# AVR_GPS_APRS_Tracker.net
KiCad netlist of a schematic drawn in EAGLE
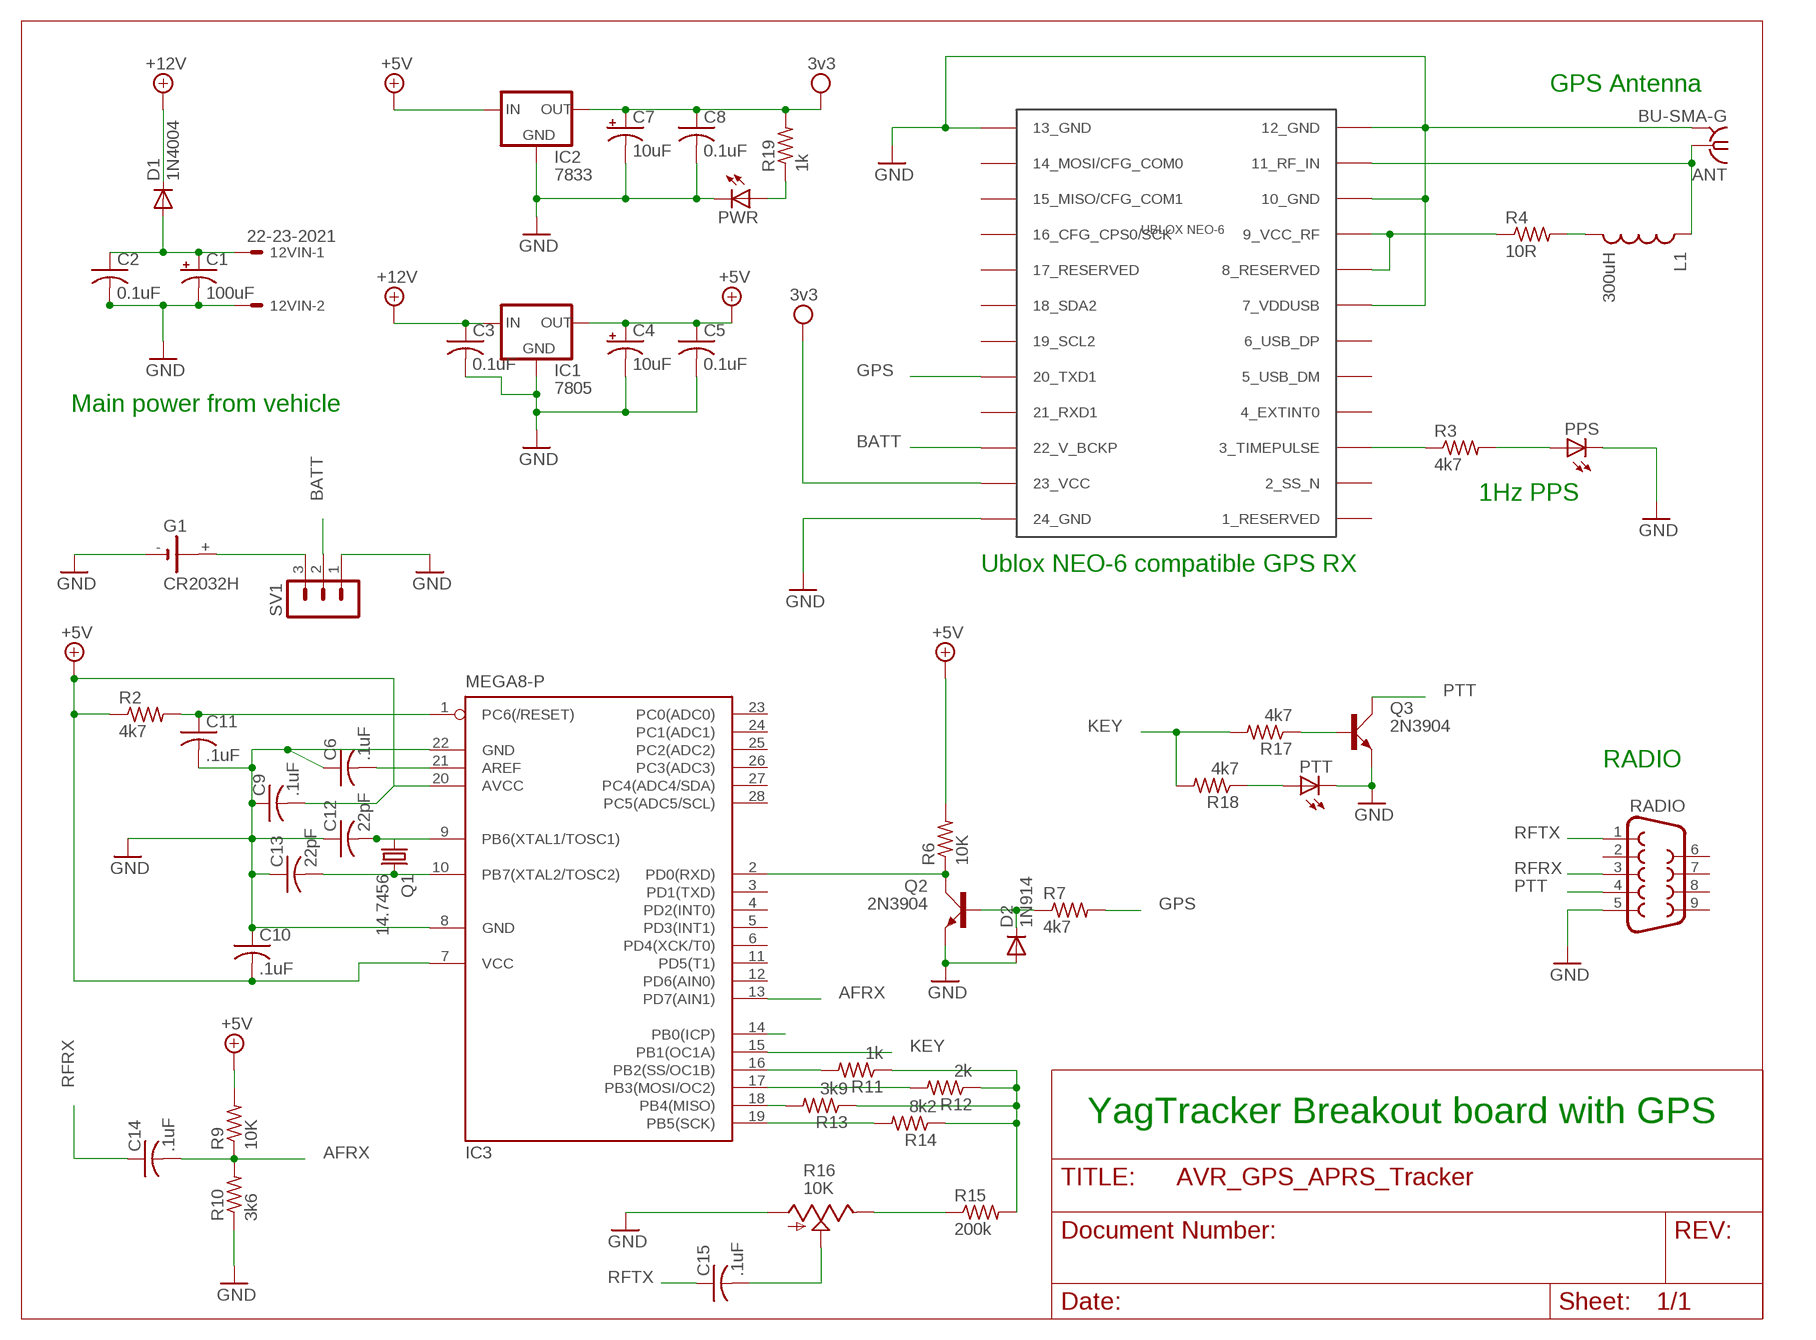
[diagram p0: schematic, sheet 1]

(export (version "E")
  (design (tool "Eeschema 10.0.6"))
  (components
    (comp (ref "12VIN")
      (value "22-23-2021")
      (footprint "eagle-import:22-23-2021")
      (fields (field (name "MF") "MOLEX"))
      (libsource (lib "eagle-import") (part "22-23-2021"))
    )
    (comp (ref "ANT")
      (value "BU-SMA-G")
      (footprint "eagle-import:BU-SMA-G")
      (libsource (lib "eagle-import") (part "BU-SMA-G"))
    )
    (comp (ref "C1")
      (value "100uF")
      (footprint "eagle-import:CPOL-RADIAL-10UF-25V")
      (libsource (lib "eagle-import") (part "CAP_POLPTH2"))
    )
    (comp (ref "C2")
      (value "0.1uF")
      (footprint "eagle-import:C025-025X050")
      (libsource (lib "eagle-import") (part "C-US025-025X050"))
    )
    (comp (ref "C3")
      (value "0.1uF")
      (footprint "eagle-import:C025-025X050")
      (libsource (lib "eagle-import") (part "C-US025-025X050"))
    )
    (comp (ref "C4")
      (value "10uF")
      (footprint "eagle-import:CPOL-RADIAL-10UF-25V")
      (libsource (lib "eagle-import") (part "CAP_POLPTH2"))
    )
    (comp (ref "C5")
      (value "0.1uF")
      (footprint "eagle-import:C025-025X050")
      (libsource (lib "eagle-import") (part "C-US025-025X050"))
    )
    (comp (ref "C6")
      (value ".1uF")
      (footprint "eagle-import:C025-025X050")
      (libsource (lib "eagle-import") (part "C-US025-025X050"))
    )
    (comp (ref "C7")
      (value "10uF")
      (footprint "eagle-import:CPOL-RADIAL-10UF-25V")
      (libsource (lib "eagle-import") (part "CAP_POLPTH2"))
    )
    (comp (ref "C8")
      (value "0.1uF")
      (footprint "eagle-import:C025-025X050")
      (libsource (lib "eagle-import") (part "C-US025-025X050"))
    )
    (comp (ref "C9")
      (value ".1uF")
      (footprint "eagle-import:C025-025X050")
      (libsource (lib "eagle-import") (part "C-US025-025X050"))
    )
    (comp (ref "C10")
      (value ".1uF")
      (footprint "eagle-import:C025-025X050")
      (libsource (lib "eagle-import") (part "C-US025-025X050"))
    )
    (comp (ref "C11")
      (value ".1uF")
      (footprint "eagle-import:C025-025X050")
      (libsource (lib "eagle-import") (part "C-US025-025X050"))
    )
    (comp (ref "C12")
      (value "22pF")
      (footprint "eagle-import:C025-025X050")
      (libsource (lib "eagle-import") (part "C-US025-025X050"))
    )
    (comp (ref "C13")
      (value "22pF")
      (footprint "eagle-import:C025-025X050")
      (libsource (lib "eagle-import") (part "C-US025-025X050"))
    )
    (comp (ref "C14")
      (value ".1uF")
      (footprint "eagle-import:C025-025X050")
      (libsource (lib "eagle-import") (part "C-US025-025X050"))
    )
    (comp (ref "C15")
      (value ".1uF")
      (footprint "eagle-import:C025-025X050")
      (libsource (lib "eagle-import") (part "C-US025-025X050"))
    )
    (comp (ref "D1")
      (value "1N4004")
      (footprint "eagle-import:DO41-10")
      (libsource (lib "eagle-import") (part "1N4004"))
    )
    (comp (ref "D2")
      (value "1N914")
      (footprint "eagle-import:D-2.5")
      (libsource (lib "eagle-import") (part "DIODE-D-2.5"))
    )
    (comp (ref "G1")
      (value "CR2032H")
      (footprint "eagle-import:CR2032H")
      (libsource (lib "eagle-import") (part "CR2032H"))
    )
    (comp (ref "IC1")
      (value "7805")
      (footprint "eagle-import:TO-220-ALT")
      (libsource (lib "eagle-import") (part "V_REG_78XX-TO-220"))
    )
    (comp (ref "IC2")
      (value "7833")
      (footprint "eagle-import:TO-220-ALT")
      (libsource (lib "eagle-import") (part "V_REG_78XX-TO-220"))
    )
    (comp (ref "IC3")
      (value "MEGA8-P")
      (footprint "eagle-import:DIL28-3")
      (libsource (lib "eagle-import") (part "MEGA8-P"))
    )
    (comp (ref "L1")
      (value "300uH")
      (footprint "eagle-import:0805")
      (libsource (lib "eagle-import") (part "INDUCTOR0805"))
    )
    (comp (ref "PPS")
      (value "LED0603")
      (footprint "eagle-import:LED-0603")
      (libsource (lib "eagle-import") (part "LED0603"))
    )
    (comp (ref "PTT")
      (value "LED3MM")
      (footprint "eagle-import:LED3MM")
      (libsource (lib "eagle-import") (part "LED3MM"))
    )
    (comp (ref "PWR")
      (value "LED3MM")
      (footprint "eagle-import:LED3MM")
      (libsource (lib "eagle-import") (part "LED3MM"))
    )
    (comp (ref "Q1")
      (value "14.7456")
      (footprint "eagle-import:HC49_S")
      (libsource (lib "eagle-import") (part "CRYSTALHC49S"))
    )
    (comp (ref "Q2")
      (value "2N3904")
      (footprint "eagle-import:TO92D")
      (libsource (lib "eagle-import") (part "2N3904"))
    )
    (comp (ref "Q3")
      (value "2N3904")
      (footprint "eagle-import:TO92D")
      (libsource (lib "eagle-import") (part "2N3904"))
    )
    (comp (ref "R2")
      (value "4k7")
      (footprint "eagle-import:0207_2V")
      (libsource (lib "eagle-import") (part "R-US_0207/2V"))
    )
    (comp (ref "R3")
      (value "4k7")
      (footprint "eagle-import:M0805")
      (libsource (lib "eagle-import") (part "R-US_M0805"))
    )
    (comp (ref "R4")
      (value "10R")
      (footprint "eagle-import:M0805")
      (libsource (lib "eagle-import") (part "R-US_M0805"))
    )
    (comp (ref "R6")
      (value "10K")
      (footprint "eagle-import:0207_2V")
      (libsource (lib "eagle-import") (part "R-US_0207/2V"))
    )
    (comp (ref "R7")
      (value "4k7")
      (footprint "eagle-import:0207_2V")
      (libsource (lib "eagle-import") (part "R-US_0207/2V"))
    )
    (comp (ref "R9")
      (value "10K")
      (footprint "eagle-import:0207_2V")
      (libsource (lib "eagle-import") (part "R-US_0207/2V"))
    )
    (comp (ref "R10")
      (value "3k6")
      (footprint "eagle-import:0207_2V")
      (libsource (lib "eagle-import") (part "R-US_0207/2V"))
    )
    (comp (ref "R11")
      (value "1k")
      (footprint "eagle-import:0207_2V")
      (libsource (lib "eagle-import") (part "R-US_0207/2V"))
    )
    (comp (ref "R12")
      (value "2k")
      (footprint "eagle-import:0207_2V")
      (libsource (lib "eagle-import") (part "R-US_0207/2V"))
    )
    (comp (ref "R13")
      (value "3k9")
      (footprint "eagle-import:0207_2V")
      (libsource (lib "eagle-import") (part "R-US_0207/2V"))
    )
    (comp (ref "R14")
      (value "8k2")
      (footprint "eagle-import:0207_2V")
      (libsource (lib "eagle-import") (part "R-US_0207/2V"))
    )
    (comp (ref "R15")
      (value "200k")
      (footprint "eagle-import:0207_2V")
      (libsource (lib "eagle-import") (part "R-US_0207/2V"))
    )
    (comp (ref "R16")
      (value "10K")
      (footprint "eagle-import:CA6V")
      (libsource (lib "eagle-import") (part "TRIM_US-CA6V"))
    )
    (comp (ref "R17")
      (value "4k7")
      (footprint "eagle-import:0207_2V")
      (libsource (lib "eagle-import") (part "R-US_0207/2V"))
    )
    (comp (ref "R18")
      (value "4k7")
      (footprint "eagle-import:0207_2V")
      (libsource (lib "eagle-import") (part "R-US_0207/2V"))
    )
    (comp (ref "R19")
      (value "1k")
      (footprint "eagle-import:0207_2V")
      (libsource (lib "eagle-import") (part "R-US_0207/2V"))
    )
    (comp (ref "RADIO")
      (value "F09HP")
      (footprint "eagle-import:F09HP")
      (libsource (lib "eagle-import") (part "F09HP"))
    )
    (comp (ref "SV1")
      (value "MA03-1")
      (footprint "eagle-import:MA03-1")
      (libsource (lib "eagle-import") (part "MA03-1"))
    )
    (comp (ref "U$1")
      (value "UBLOX_NEO-6")
      (footprint "eagle-import:UBLOX_NEO-6P")
      (libsource (lib "eagle-import") (part "UBLOX_NEO-6"))
    )
  )
  (nets
    (net (code "1") (name "+5V") (class "Default")
      (node (ref "C10") (pin "2") (pinfunction "2_2") (pintype "passive"))
      (node (ref "C4") (pin "1") (pinfunction "+_1") (pintype "passive"))
      (node (ref "C5") (pin "1") (pinfunction "1_1") (pintype "passive"))
      (node (ref "C9") (pin "2") (pinfunction "2_2") (pintype "passive"))
      (node (ref "IC1") (pin "OUT") (pinfunction "OUT_OUT") (pintype "output"))
      (node (ref "IC2") (pin "IN") (pinfunction "IN_IN") (pintype "input"))
      (node (ref "IC3") (pin "20") (pinfunction "AVCC_20") (pintype "power_in"))
      (node (ref "IC3") (pin "7") (pinfunction "VCC_7") (pintype "power_in"))
      (node (ref "R2") (pin "1") (pinfunction "1_1") (pintype "passive"))
      (node (ref "R6") (pin "2") (pinfunction "2_2") (pintype "passive"))
      (node (ref "R9") (pin "2") (pinfunction "2_2") (pintype "passive"))
    )
    (net (code "2") (name "+12V") (class "Default")
      (node (ref "C3") (pin "1") (pinfunction "1_1") (pintype "passive"))
      (node (ref "D1") (pin "C") (pinfunction "C_C") (pintype "passive"))
      (node (ref "IC1") (pin "IN") (pinfunction "IN_IN") (pintype "input"))
    )
    (net (code "3") (name "/AFRX") (class "Default")
      (node (ref "C14") (pin "2") (pinfunction "2_2") (pintype "passive"))
      (node (ref "IC3") (pin "13") (pinfunction "PD7(AIN1)_13") (pintype "bidirectional"))
      (node (ref "R10") (pin "2") (pinfunction "2_2") (pintype "passive"))
      (node (ref "R9") (pin "1") (pinfunction "1_1") (pintype "passive"))
    )
    (net (code "4") (name "/BATT") (class "Default")
      (node (ref "SV1") (pin "2") (pinfunction "2_2") (pintype "passive"))
      (node (ref "U$1") (pin "22_V_BCKP") (pinfunction "22_V_BCKP_22_V_BCKP") (pintype "bidirectional"))
    )
    (net (code "5") (name "/GPS") (class "Default")
      (node (ref "R7") (pin "2") (pinfunction "2_2") (pintype "passive"))
      (node (ref "U$1") (pin "20_TXD1") (pinfunction "20_TXD1_20_TXD1") (pintype "bidirectional"))
    )
    (net (code "6") (name "/KEY") (class "Default")
      (node (ref "IC3") (pin "15") (pinfunction "PB1(OC1A)_15") (pintype "bidirectional"))
      (node (ref "R17") (pin "2") (pinfunction "2_2") (pintype "passive"))
      (node (ref "R18") (pin "2") (pinfunction "2_2") (pintype "passive"))
    )
    (net (code "7") (name "/PTT") (class "Default")
      (node (ref "Q3") (pin "C") (pinfunction "C_C") (pintype "passive"))
      (node (ref "RADIO") (pin "4") (pinfunction "4_4") (pintype "passive"))
    )
    (net (code "8") (name "/RFRX") (class "Default")
      (node (ref "C14") (pin "1") (pinfunction "1_1") (pintype "passive"))
      (node (ref "RADIO") (pin "3") (pinfunction "3_3") (pintype "passive"))
    )
    (net (code "9") (name "/RFTX") (class "Default")
      (node (ref "C15") (pin "1") (pinfunction "1_1") (pintype "passive"))
      (node (ref "RADIO") (pin "1") (pinfunction "1_1") (pintype "passive"))
    )
    (net (code "10") (name "3v3") (class "Default")
      (node (ref "C7") (pin "1") (pinfunction "+_1") (pintype "passive"))
      (node (ref "C8") (pin "1") (pinfunction "1_1") (pintype "passive"))
      (node (ref "IC2") (pin "OUT") (pinfunction "OUT_OUT") (pintype "output"))
      (node (ref "R19") (pin "2") (pinfunction "2_2") (pintype "passive"))
      (node (ref "U$1") (pin "23_VCC") (pinfunction "23_VCC_23_VCC") (pintype "bidirectional"))
    )
    (net (code "11") (name "GND") (class "Default")
      (node (ref "12VIN") (pin "2") (pinfunction "S_2") (pintype "passive"))
      (node (ref "ANT") (pin "2") (pinfunction "GND_2") (pintype "power_in"))
      (node (ref "C1") (pin "2") (pinfunction "-_2") (pintype "passive"))
      (node (ref "C10") (pin "1") (pinfunction "1_1") (pintype "passive"))
      (node (ref "C11") (pin "2") (pinfunction "2_2") (pintype "passive"))
      (node (ref "C12") (pin "1") (pinfunction "1_1") (pintype "passive"))
      (node (ref "C13") (pin "1") (pinfunction "1_1") (pintype "passive"))
      (node (ref "C2") (pin "2") (pinfunction "2_2") (pintype "passive"))
      (node (ref "C3") (pin "2") (pinfunction "2_2") (pintype "passive"))
      (node (ref "C4") (pin "2") (pinfunction "-_2") (pintype "passive"))
      (node (ref "C5") (pin "2") (pinfunction "2_2") (pintype "passive"))
      (node (ref "C6") (pin "1") (pinfunction "1_1") (pintype "passive"))
      (node (ref "C7") (pin "2") (pinfunction "-_2") (pintype "passive"))
      (node (ref "C8") (pin "2") (pinfunction "2_2") (pintype "passive"))
      (node (ref "C9") (pin "1") (pinfunction "1_1") (pintype "passive"))
      (node (ref "D2") (pin "A") (pinfunction "A_A") (pintype "passive"))
      (node (ref "G1") (pin "-") (pinfunction "-_-") (pintype "passive"))
      (node (ref "IC1") (pin "GND") (pinfunction "GND_GND") (pintype "input"))
      (node (ref "IC2") (pin "GND") (pinfunction "GND_GND") (pintype "input"))
      (node (ref "IC3") (pin "22") (pinfunction "GND_22") (pintype "power_in"))
      (node (ref "IC3") (pin "8") (pinfunction "GND_8") (pintype "power_in"))
      (node (ref "PPS") (pin "C") (pinfunction "C_C") (pintype "passive"))
      (node (ref "PTT") (pin "K") (pinfunction "C_K") (pintype "passive"))
      (node (ref "PWR") (pin "K") (pinfunction "C_K") (pintype "passive"))
      (node (ref "Q2") (pin "E") (pinfunction "E_E") (pintype "passive"))
      (node (ref "Q3") (pin "E") (pinfunction "E_E") (pintype "passive"))
      (node (ref "R10") (pin "1") (pinfunction "1_1") (pintype "passive"))
      (node (ref "R16") (pin "A") (pinfunction "A_A") (pintype "passive"))
      (node (ref "RADIO") (pin "5") (pinfunction "5_5") (pintype "passive"))
      (node (ref "SV1") (pin "1") (pinfunction "1_1") (pintype "passive"))
      (node (ref "U$1") (pin "10_GND") (pinfunction "10_GND_10_GND") (pintype "bidirectional"))
      (node (ref "U$1") (pin "12_GND") (pinfunction "12_GND_12_GND") (pintype "bidirectional"))
      (node (ref "U$1") (pin "13_GND") (pinfunction "13_GND_13_GND") (pintype "bidirectional"))
      (node (ref "U$1") (pin "24_GND") (pinfunction "24_GND_24_GND") (pintype "bidirectional"))
      (node (ref "U$1") (pin "7_VDDUSB") (pinfunction "7_VDDUSB_7_VDDUSB") (pintype "bidirectional"))
    )
    (net (code "12") (name "Net-(12VINA-S)") (class "Default")
      (node (ref "12VIN") (pin "1") (pinfunction "S_1") (pintype "passive"))
      (node (ref "C1") (pin "1") (pinfunction "+_1") (pintype "passive"))
      (node (ref "C2") (pin "1") (pinfunction "1_1") (pintype "passive"))
      (node (ref "D1") (pin "A") (pinfunction "A_A") (pintype "passive"))
    )
    (net (code "13") (name "Net-(ANT-Pad1)") (class "Default")
      (node (ref "ANT") (pin "1") (pinfunction "1_1") (pintype "passive"))
      (node (ref "L1") (pin "1") (pinfunction "1_1") (pintype "passive"))
      (node (ref "U$1") (pin "11_RF_IN") (pinfunction "11_RF_IN_11_RF_IN") (pintype "bidirectional"))
    )
    (net (code "14") (name "Net-(C15-Pad2)") (class "Default")
      (node (ref "C15") (pin "2") (pinfunction "2_2") (pintype "passive"))
      (node (ref "R16") (pin "S") (pinfunction "S_S") (pintype "passive"))
    )
    (net (code "15") (name "Net-(D2-PadC)") (class "Default")
      (node (ref "D2") (pin "C") (pinfunction "C_C") (pintype "passive"))
      (node (ref "Q2") (pin "B") (pinfunction "B_B") (pintype "passive"))
      (node (ref "R7") (pin "1") (pinfunction "1_1") (pintype "passive"))
    )
    (net (code "16") (name "Net-(G1-Pad+)") (class "Default")
      (node (ref "G1") (pin "+") (pinfunction "+_+") (pintype "passive"))
      (node (ref "SV1") (pin "3") (pinfunction "3_3") (pintype "passive"))
    )
    (net (code "17") (name "Net-(IC3-AREF)") (class "Default")
      (node (ref "C6") (pin "2") (pinfunction "2_2") (pintype "passive"))
      (node (ref "IC3") (pin "21") (pinfunction "AREF_21") (pintype "passive"))
    )
    (net (code "18") (name "Net-(IC3-PB2(SS{slash}OC1B))") (class "Default")
      (node (ref "IC3") (pin "16") (pinfunction "PB2(SS/OC1B)_16") (pintype "bidirectional"))
      (node (ref "R11") (pin "2") (pinfunction "2_2") (pintype "passive"))
    )
    (net (code "19") (name "Net-(IC3-PB3(MOSI{slash}OC2))") (class "Default")
      (node (ref "IC3") (pin "17") (pinfunction "PB3(MOSI/OC2)_17") (pintype "bidirectional"))
      (node (ref "R12") (pin "2") (pinfunction "2_2") (pintype "passive"))
    )
    (net (code "20") (name "Net-(IC3-PB4(MISO))") (class "Default")
      (node (ref "IC3") (pin "18") (pinfunction "PB4(MISO)_18") (pintype "bidirectional"))
      (node (ref "R13") (pin "2") (pinfunction "2_2") (pintype "passive"))
    )
    (net (code "21") (name "Net-(IC3-PB5(SCK))") (class "Default")
      (node (ref "IC3") (pin "19") (pinfunction "PB5(SCK)_19") (pintype "bidirectional"))
      (node (ref "R14") (pin "2") (pinfunction "2_2") (pintype "passive"))
    )
    (net (code "22") (name "Net-(IC3-PB6(XTAL1{slash}TOSC1))") (class "Default")
      (node (ref "C12") (pin "2") (pinfunction "2_2") (pintype "passive"))
      (node (ref "IC3") (pin "9") (pinfunction "PB6(XTAL1/TOSC1)_9") (pintype "bidirectional"))
      (node (ref "Q1") (pin "1") (pinfunction "1_1") (pintype "passive"))
    )
    (net (code "23") (name "Net-(IC3-PB7(XTAL2{slash}TOSC2))") (class "Default")
      (node (ref "C13") (pin "2") (pinfunction "2_2") (pintype "passive"))
      (node (ref "IC3") (pin "10") (pinfunction "PB7(XTAL2/TOSC2)_10") (pintype "bidirectional"))
      (node (ref "Q1") (pin "2") (pinfunction "2_2") (pintype "passive"))
    )
    (net (code "24") (name "Net-(IC3-PC6({slash}RESET))") (class "Default")
      (node (ref "C11") (pin "1") (pinfunction "1_1") (pintype "passive"))
      (node (ref "IC3") (pin "1") (pinfunction "PC6(/RESET)_1") (pintype "bidirectional"))
      (node (ref "R2") (pin "2") (pinfunction "2_2") (pintype "passive"))
    )
    (net (code "25") (name "Net-(IC3-PD0(RXD))") (class "Default")
      (node (ref "IC3") (pin "2") (pinfunction "PD0(RXD)_2") (pintype "bidirectional"))
      (node (ref "Q2") (pin "C") (pinfunction "C_C") (pintype "passive"))
      (node (ref "R6") (pin "1") (pinfunction "1_1") (pintype "passive"))
    )
    (net (code "26") (name "Net-(L1-Pad2)") (class "Default")
      (node (ref "L1") (pin "2") (pinfunction "2_2") (pintype "passive"))
      (node (ref "R4") (pin "2") (pinfunction "2_2") (pintype "passive"))
    )
    (net (code "27") (name "Net-(PPS-PadA)") (class "Default")
      (node (ref "PPS") (pin "A") (pinfunction "A_A") (pintype "passive"))
      (node (ref "R3") (pin "2") (pinfunction "2_2") (pintype "passive"))
    )
    (net (code "28") (name "Net-(PTT-PadA)") (class "Default")
      (node (ref "PTT") (pin "A") (pinfunction "A_A") (pintype "passive"))
      (node (ref "R18") (pin "1") (pinfunction "1_1") (pintype "passive"))
    )
    (net (code "29") (name "Net-(PWR-PadA)") (class "Default")
      (node (ref "PWR") (pin "A") (pinfunction "A_A") (pintype "passive"))
      (node (ref "R19") (pin "1") (pinfunction "1_1") (pintype "passive"))
    )
    (net (code "30") (name "Net-(Q3-PadB)") (class "Default")
      (node (ref "Q3") (pin "B") (pinfunction "B_B") (pintype "passive"))
      (node (ref "R17") (pin "1") (pinfunction "1_1") (pintype "passive"))
    )
    (net (code "31") (name "Net-(R3-Pad1)") (class "Default")
      (node (ref "R3") (pin "1") (pinfunction "1_1") (pintype "passive"))
      (node (ref "U$1") (pin "3_TIMEPULSE") (pinfunction "3_TIMEPULSE_3_TIMEPULSE") (pintype "bidirectional"))
    )
    (net (code "32") (name "Net-(R4-Pad1)") (class "Default")
      (node (ref "R4") (pin "1") (pinfunction "1_1") (pintype "passive"))
      (node (ref "U$1") (pin "8_RESERVED") (pinfunction "8_RESERVED_8_RESERVED") (pintype "bidirectional"))
      (node (ref "U$1") (pin "9_VCC_RF") (pinfunction "9_VCC_RF_9_VCC_RF") (pintype "bidirectional"))
    )
    (net (code "33") (name "Net-(R11-Pad1)") (class "Default")
      (node (ref "R11") (pin "1") (pinfunction "1_1") (pintype "passive"))
      (node (ref "R12") (pin "1") (pinfunction "1_1") (pintype "passive"))
      (node (ref "R13") (pin "1") (pinfunction "1_1") (pintype "passive"))
      (node (ref "R14") (pin "1") (pinfunction "1_1") (pintype "passive"))
      (node (ref "R15") (pin "2") (pinfunction "2_2") (pintype "passive"))
    )
    (net (code "34") (name "Net-(R15-Pad1)") (class "Default")
      (node (ref "R15") (pin "1") (pinfunction "1_1") (pintype "passive"))
      (node (ref "R16") (pin "E") (pinfunction "E_E") (pintype "passive"))
    )
    (net (code "35") (name "unconnected-(G1-+-Pad+@1)") (class "Default")
      (node (ref "G1") (pin "+@1") (pinfunction "+_+@1") (pintype "passive"))
    )
    (net (code "36") (name "unconnected-(IC3-PB0(ICP)-Pad14)") (class "Default")
      (node (ref "IC3") (pin "14") (pinfunction "PB0(ICP)_14") (pintype "bidirectional"))
    )
    (net (code "37") (name "unconnected-(IC3-PC0(ADC0)-Pad23)") (class "Default")
      (node (ref "IC3") (pin "23") (pinfunction "PC0(ADC0)_23") (pintype "bidirectional"))
    )
    (net (code "38") (name "unconnected-(IC3-PC1(ADC1)-Pad24)") (class "Default")
      (node (ref "IC3") (pin "24") (pinfunction "PC1(ADC1)_24") (pintype "bidirectional"))
    )
    (net (code "39") (name "unconnected-(IC3-PC2(ADC2)-Pad25)") (class "Default")
      (node (ref "IC3") (pin "25") (pinfunction "PC2(ADC2)_25") (pintype "bidirectional"))
    )
    (net (code "40") (name "unconnected-(IC3-PC3(ADC3)-Pad26)") (class "Default")
      (node (ref "IC3") (pin "26") (pinfunction "PC3(ADC3)_26") (pintype "bidirectional"))
    )
    (net (code "41") (name "unconnected-(IC3-PC4(ADC4{slash}SDA)-Pad27)") (class "Default")
      (node (ref "IC3") (pin "27") (pinfunction "PC4(ADC4/SDA)_27") (pintype "bidirectional"))
    )
    (net (code "42") (name "unconnected-(IC3-PC5(ADC5{slash}SCL)-Pad28)") (class "Default")
      (node (ref "IC3") (pin "28") (pinfunction "PC5(ADC5/SCL)_28") (pintype "bidirectional"))
    )
    (net (code "43") (name "unconnected-(IC3-PD1(TXD)-Pad3)") (class "Default")
      (node (ref "IC3") (pin "3") (pinfunction "PD1(TXD)_3") (pintype "bidirectional"))
    )
    (net (code "44") (name "unconnected-(IC3-PD2(INT0)-Pad4)") (class "Default")
      (node (ref "IC3") (pin "4") (pinfunction "PD2(INT0)_4") (pintype "bidirectional"))
    )
    (net (code "45") (name "unconnected-(IC3-PD3(INT1)-Pad5)") (class "Default")
      (node (ref "IC3") (pin "5") (pinfunction "PD3(INT1)_5") (pintype "bidirectional"))
    )
    (net (code "46") (name "unconnected-(IC3-PD4(XCK{slash}T0)-Pad6)") (class "Default")
      (node (ref "IC3") (pin "6") (pinfunction "PD4(XCK/T0)_6") (pintype "bidirectional"))
    )
    (net (code "47") (name "unconnected-(IC3-PD5(T1)-Pad11)") (class "Default")
      (node (ref "IC3") (pin "11") (pinfunction "PD5(T1)_11") (pintype "bidirectional"))
    )
    (net (code "48") (name "unconnected-(IC3-PD6(AIN0)-Pad12)") (class "Default")
      (node (ref "IC3") (pin "12") (pinfunction "PD6(AIN0)_12") (pintype "bidirectional"))
    )
    (net (code "49") (name "unconnected-(RADIO-Pad2)") (class "Default")
      (node (ref "RADIO") (pin "2") (pinfunction "2_2") (pintype "passive"))
    )
    (net (code "50") (name "unconnected-(RADIO-Pad6)") (class "Default")
      (node (ref "RADIO") (pin "6") (pinfunction "6_6") (pintype "passive"))
    )
    (net (code "51") (name "unconnected-(RADIO-Pad7)") (class "Default")
      (node (ref "RADIO") (pin "7") (pinfunction "7_7") (pintype "passive"))
    )
    (net (code "52") (name "unconnected-(RADIO-Pad8)") (class "Default")
      (node (ref "RADIO") (pin "8") (pinfunction "8_8") (pintype "passive"))
    )
    (net (code "53") (name "unconnected-(RADIO-Pad9)") (class "Default")
      (node (ref "RADIO") (pin "9") (pinfunction "9_9") (pintype "passive"))
    )
    (net (code "54") (name "unconnected-(U$1-Pad1_RESERVED)") (class "Default")
      (node (ref "U$1") (pin "1_RESERVED") (pinfunction "1_RESERVED_1_RESERVED") (pintype "bidirectional"))
    )
    (net (code "55") (name "unconnected-(U$1-Pad2_SS_N)") (class "Default")
      (node (ref "U$1") (pin "2_SS_N") (pinfunction "2_SS_N_2_SS_N") (pintype "bidirectional"))
    )
    (net (code "56") (name "unconnected-(U$1-Pad4_EXTINT0)") (class "Default")
      (node (ref "U$1") (pin "4_EXTINT0") (pinfunction "4_EXTINT0_4_EXTINT0") (pintype "bidirectional"))
    )
    (net (code "57") (name "unconnected-(U$1-Pad5_USB_DM)") (class "Default")
      (node (ref "U$1") (pin "5_USB_DM") (pinfunction "5_USB_DM_5_USB_DM") (pintype "bidirectional"))
    )
    (net (code "58") (name "unconnected-(U$1-Pad6_USB_DP)") (class "Default")
      (node (ref "U$1") (pin "6_USB_DP") (pinfunction "6_USB_DP_6_USB_DP") (pintype "bidirectional"))
    )
    (net (code "59") (name "unconnected-(U$1-Pad14_MOSI{slash}CFG_COM0)") (class "Default")
      (node (ref "U$1") (pin "14_MOSI/CFG_COM0") (pinfunction "14_MOSI/CFG_COM0_14_MOSI/CFG_COM0") (pintype "bidirectional"))
    )
    (net (code "60") (name "unconnected-(U$1-Pad15_MISO{slash}CFG_COM1)") (class "Default")
      (node (ref "U$1") (pin "15_MISO/CFG_COM1") (pinfunction "15_MISO/CFG_COM1_15_MISO/CFG_COM1") (pintype "bidirectional"))
    )
    (net (code "61") (name "unconnected-(U$1-Pad16_CFG_CPS0{slash}SCK)") (class "Default")
      (node (ref "U$1") (pin "16_CFG_CPS0/SCK") (pinfunction "16_CFG_CPS0/SCK_16_CFG_CPS0/SCK") (pintype "bidirectional"))
    )
    (net (code "62") (name "unconnected-(U$1-Pad17_RESERVED)") (class "Default")
      (node (ref "U$1") (pin "17_RESERVED") (pinfunction "17_RESERVED_17_RESERVED") (pintype "bidirectional"))
    )
    (net (code "63") (name "unconnected-(U$1-Pad18_SDA2)") (class "Default")
      (node (ref "U$1") (pin "18_SDA2") (pinfunction "18_SDA2_18_SDA2") (pintype "bidirectional"))
    )
    (net (code "64") (name "unconnected-(U$1-Pad19_SCL2)") (class "Default")
      (node (ref "U$1") (pin "19_SCL2") (pinfunction "19_SCL2_19_SCL2") (pintype "bidirectional"))
    )
    (net (code "65") (name "unconnected-(U$1-Pad21_RXD1)") (class "Default")
      (node (ref "U$1") (pin "21_RXD1") (pinfunction "21_RXD1_21_RXD1") (pintype "bidirectional"))
    )
  )
)
